# TempSense.net
KiCad netlist of a schematic drawn in Altium Designer
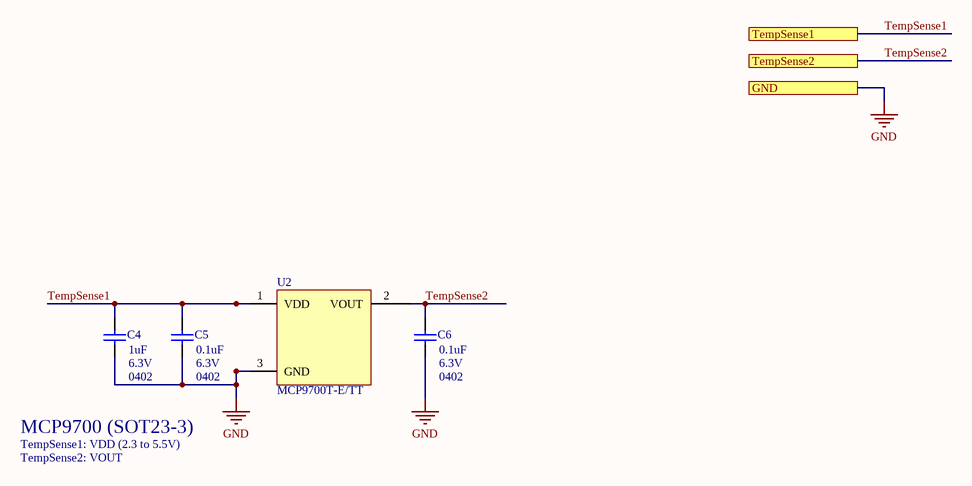
[diagram p0: TempSense.SchDoc]

(export (version "E")
  (design (tool "Eeschema 10.0.6"))
  (components
    (comp (ref "C4")
      (value "1uF")
      (footprint "CAPC1005X06N")
      (description "General purpose capacitor")
      (fields
        (field (name "RATED VOLTAGE") "6.3V")
        (field (name "PACKAGE") "0402")
        (field (name "Comment") "Capacitor")
      )
      (libsource (lib "Schematic_Generic") (part "Capacitor"))
    )
    (comp (ref "C5")
      (value "0.1uF")
      (footprint "CAPC1005X06N")
      (description "General purpose capacitor")
      (fields
        (field (name "RATED VOLTAGE") "6.3V")
        (field (name "PACKAGE") "0402")
        (field (name "Comment") "Capacitor")
      )
      (libsource (lib "Schematic_Generic") (part "Capacitor"))
    )
    (comp (ref "C6")
      (value "0.1uF")
      (footprint "CAPC1005X06N")
      (description "General purpose capacitor")
      (fields
        (field (name "RATED VOLTAGE") "6.3V")
        (field (name "PACKAGE") "0402")
        (field (name "Comment") "Capacitor")
      )
      (libsource (lib "Schematic_Generic") (part "Capacitor"))
    )
    (comp (ref "U2")
      (value "MCP9700T-E/TT")
      (footprint "SOT95P237X112-3N")
      (description "Low-Power Linear Active Thermistor IC, SOT-23-3 package")
      (libsource (lib "WiirdFlex") (part "MCP9700T-E/TT"))
    )
  )
  (nets
    (net (code "1") (name "/TempSense1") (class "Default")
      (node (ref "C4") (pin "2") (pinfunction "2_2") (pintype "passive"))
      (node (ref "C5") (pin "2") (pinfunction "2_2") (pintype "passive"))
      (node (ref "U2") (pin "1") (pinfunction "VDD_1") (pintype "passive"))
    )
    (net (code "2") (name "/TempSense2") (class "Default")
      (node (ref "C6") (pin "2") (pinfunction "2_2") (pintype "passive"))
      (node (ref "U2") (pin "2") (pinfunction "VOUT_2") (pintype "passive"))
    )
    (net (code "3") (name "GND") (class "Default")
      (node (ref "C4") (pin "1") (pinfunction "1_1") (pintype "passive"))
      (node (ref "C5") (pin "1") (pinfunction "1_1") (pintype "passive"))
      (node (ref "C6") (pin "1") (pinfunction "1_1") (pintype "passive"))
      (node (ref "U2") (pin "3") (pinfunction "GND_3") (pintype "passive"))
    )
  )
)
